# darwin-sonar-sensor.net
KiCad netlist of a schematic drawn in EAGLE
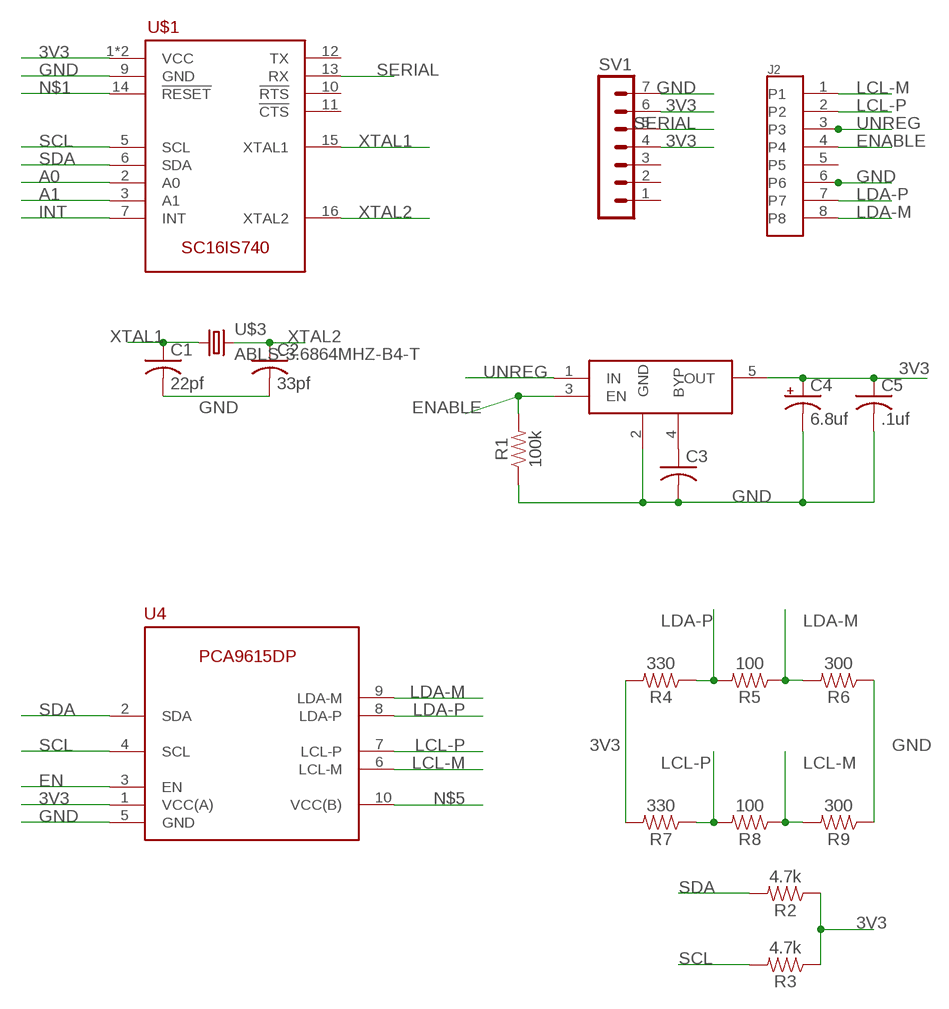
[diagram p0: schematic, sheet 1]

(export (version "E")
  (design (tool "Eeschema 10.0.6"))
  (components
    (comp (ref "C1")
      (value "22pf")
      (footprint "eagle-import:C0603K")
      (libsource (lib "eagle-import") (part "C-USC0603K"))
    )
    (comp (ref "C2")
      (value "33pf")
      (footprint "eagle-import:C0603K")
      (libsource (lib "eagle-import") (part "C-USC0603K"))
    )
    (comp (ref "C3")
      (value "C-USC0603K")
      (footprint "eagle-import:C0603K")
      (libsource (lib "eagle-import") (part "C-USC0603K"))
    )
    (comp (ref "C4")
      (value "6.8uf")
      (footprint "eagle-import:A_3216-18R")
      (libsource (lib "eagle-import") (part "CPOL-USA/3216-18R"))
    )
    (comp (ref "C5")
      (value ".1uf")
      (footprint "eagle-import:C0603K")
      (libsource (lib "eagle-import") (part "C-USC0603K"))
    )
    (comp (ref "J2")
      (value "95501-6889VERT")
      (footprint "eagle-import:85513-5009")
      (libsource (lib "eagle-import") (part "95501-6889VERT"))
    )
    (comp (ref "R1")
      (value "100k")
      (footprint "eagle-import:0603")
      (libsource (lib "eagle-import") (part "100KOHM-0603-1/10W-1%"))
    )
    (comp (ref "R2")
      (value "4.7k")
      (footprint "eagle-import:0603")
      (libsource (lib "eagle-import") (part "100KOHM-0603-1/10W-1%"))
    )
    (comp (ref "R3")
      (value "4.7k")
      (footprint "eagle-import:0603")
      (libsource (lib "eagle-import") (part "100KOHM-0603-1/10W-1%"))
    )
    (comp (ref "R4")
      (value "330")
      (footprint "eagle-import:0603")
      (libsource (lib "eagle-import") (part "100KOHM-0603-1/10W-1%"))
    )
    (comp (ref "R5")
      (value "100")
      (footprint "eagle-import:0603")
      (libsource (lib "eagle-import") (part "100KOHM-0603-1/10W-1%"))
    )
    (comp (ref "R6")
      (value "300")
      (footprint "eagle-import:0603")
      (libsource (lib "eagle-import") (part "100KOHM-0603-1/10W-1%"))
    )
    (comp (ref "R7")
      (value "330")
      (footprint "eagle-import:0603")
      (libsource (lib "eagle-import") (part "100KOHM-0603-1/10W-1%"))
    )
    (comp (ref "R8")
      (value "100")
      (footprint "eagle-import:0603")
      (libsource (lib "eagle-import") (part "100KOHM-0603-1/10W-1%"))
    )
    (comp (ref "R9")
      (value "300")
      (footprint "eagle-import:0603")
      (libsource (lib "eagle-import") (part "100KOHM-0603-1/10W-1%"))
    )
    (comp (ref "SV1")
      (value "MA07-1")
      (footprint "eagle-import:MA07-1")
      (libsource (lib "eagle-import") (part "MA07-1"))
    )
    (comp (ref "U$1")
      (value "SC16IS740")
      (footprint "eagle-import:SOP65P640X110-16")
      (libsource (lib "eagle-import") (part "SC16IS740"))
    )
    (comp (ref "U$3")
      (value "ABLS-3.6864MHZ-B4-T")
      (footprint "eagle-import:ABLS")
      (libsource (lib "eagle-import") (part "ABLS-3.6864MHZ-B4-T"))
    )
    (comp (ref "U$4")
      (value "MIC5219-3.3YM5-TR")
      (footprint "eagle-import:SOT95P280X145-5")
      (libsource (lib "eagle-import") (part "MIC5219-3.3YM5-TR"))
    )
    (comp (ref "U4")
      (value "PCA9615")
      (footprint "eagle-import:SOP50P490X110-10")
      (libsource (lib "eagle-import") (part "PCA9615"))
    )
  )
  (nets
    (net (code "1") (name "/3V3") (class "Default")
      (node (ref "C4") (pin "+") (pinfunction "+_+") (pintype "passive"))
      (node (ref "C5") (pin "1") (pinfunction "1_1") (pintype "passive"))
      (node (ref "R2") (pin "1") (pinfunction "1_1") (pintype "passive"))
      (node (ref "R3") (pin "1") (pinfunction "1_1") (pintype "passive"))
      (node (ref "R4") (pin "2") (pinfunction "2_2") (pintype "passive"))
      (node (ref "R7") (pin "2") (pinfunction "2_2") (pintype "passive"))
      (node (ref "SV1") (pin "4") (pinfunction "4_4") (pintype "passive"))
      (node (ref "SV1") (pin "6") (pinfunction "6_6") (pintype "passive"))
      (node (ref "U$1") (pin "1") (pinfunction "VCC_1") (pintype "bidirectional"))
      (node (ref "U$1") (pin "8") (pinfunction "VCC_8") (pintype "bidirectional"))
      (node (ref "U$4") (pin "5") (pinfunction "OUT_5") (pintype "bidirectional"))
      (node (ref "U4") (pin "1") (pinfunction "VCC(A)_1") (pintype "bidirectional"))
    )
    (net (code "2") (name "/A0") (class "Default")
      (node (ref "U$1") (pin "2") (pinfunction "A0_2") (pintype "bidirectional"))
    )
    (net (code "3") (name "/A1") (class "Default")
      (node (ref "U$1") (pin "3") (pinfunction "A1_3") (pintype "bidirectional"))
    )
    (net (code "4") (name "/EN") (class "Default")
      (node (ref "U4") (pin "3") (pinfunction "EN_3") (pintype "bidirectional"))
    )
    (net (code "5") (name "/ENABLE") (class "Default")
      (node (ref "J2") (pin "4") (pinfunction "P4_4") (pintype "bidirectional"))
      (node (ref "R1") (pin "2") (pinfunction "2_2") (pintype "passive"))
      (node (ref "U$4") (pin "3") (pinfunction "EN_3") (pintype "bidirectional"))
    )
    (net (code "6") (name "/GND") (class "Default")
      (node (ref "C1") (pin "2") (pinfunction "2_2") (pintype "passive"))
      (node (ref "C2") (pin "2") (pinfunction "2_2") (pintype "passive"))
      (node (ref "C3") (pin "2") (pinfunction "2_2") (pintype "passive"))
      (node (ref "C4") (pin "-") (pinfunction "-_-") (pintype "passive"))
      (node (ref "C5") (pin "2") (pinfunction "2_2") (pintype "passive"))
      (node (ref "J2") (pin "6") (pinfunction "P6_6") (pintype "bidirectional"))
      (node (ref "R1") (pin "1") (pinfunction "1_1") (pintype "passive"))
      (node (ref "R6") (pin "1") (pinfunction "1_1") (pintype "passive"))
      (node (ref "R9") (pin "1") (pinfunction "1_1") (pintype "passive"))
      (node (ref "SV1") (pin "7") (pinfunction "7_7") (pintype "passive"))
      (node (ref "U$1") (pin "9") (pinfunction "GND_9") (pintype "bidirectional"))
      (node (ref "U$4") (pin "2") (pinfunction "GND_2") (pintype "bidirectional"))
      (node (ref "U4") (pin "5") (pinfunction "GND_5") (pintype "bidirectional"))
    )
    (net (code "7") (name "/INT") (class "Default")
      (node (ref "U$1") (pin "7") (pinfunction "INT_7") (pintype "bidirectional"))
    )
    (net (code "8") (name "/LCL-M") (class "Default")
      (node (ref "J2") (pin "1") (pinfunction "P1_1") (pintype "bidirectional"))
      (node (ref "R8") (pin "1") (pinfunction "1_1") (pintype "passive"))
      (node (ref "R9") (pin "2") (pinfunction "2_2") (pintype "passive"))
      (node (ref "U4") (pin "6") (pinfunction "LCL-M_6") (pintype "bidirectional"))
    )
    (net (code "9") (name "/LCL-P") (class "Default")
      (node (ref "J2") (pin "2") (pinfunction "P2_2") (pintype "bidirectional"))
      (node (ref "R7") (pin "1") (pinfunction "1_1") (pintype "passive"))
      (node (ref "R8") (pin "2") (pinfunction "2_2") (pintype "passive"))
      (node (ref "U4") (pin "7") (pinfunction "LCL-P_7") (pintype "bidirectional"))
    )
    (net (code "10") (name "/LDA-M") (class "Default")
      (node (ref "J2") (pin "8") (pinfunction "P8_8") (pintype "bidirectional"))
      (node (ref "R5") (pin "1") (pinfunction "1_1") (pintype "passive"))
      (node (ref "R6") (pin "2") (pinfunction "2_2") (pintype "passive"))
      (node (ref "U4") (pin "9") (pinfunction "LDA-M_9") (pintype "bidirectional"))
    )
    (net (code "11") (name "/LDA-P") (class "Default")
      (node (ref "J2") (pin "7") (pinfunction "P7_7") (pintype "bidirectional"))
      (node (ref "R4") (pin "1") (pinfunction "1_1") (pintype "passive"))
      (node (ref "R5") (pin "2") (pinfunction "2_2") (pintype "passive"))
      (node (ref "U4") (pin "8") (pinfunction "LDA-P_8") (pintype "bidirectional"))
    )
    (net (code "12") (name "/N$1") (class "Default")
      (node (ref "U$1") (pin "14") (pinfunction "~{RESET}_14") (pintype "bidirectional"))
    )
    (net (code "13") (name "/N$5") (class "Default")
      (node (ref "U4") (pin "10") (pinfunction "VCC(B)_10") (pintype "bidirectional"))
    )
    (net (code "14") (name "/SCL") (class "Default")
      (node (ref "R3") (pin "2") (pinfunction "2_2") (pintype "passive"))
      (node (ref "U$1") (pin "5") (pinfunction "SCL_5") (pintype "bidirectional"))
      (node (ref "U4") (pin "4") (pinfunction "SCL_4") (pintype "bidirectional"))
    )
    (net (code "15") (name "/SDA") (class "Default")
      (node (ref "R2") (pin "2") (pinfunction "2_2") (pintype "passive"))
      (node (ref "U$1") (pin "6") (pinfunction "SDA_6") (pintype "bidirectional"))
      (node (ref "U4") (pin "2") (pinfunction "SDA_2") (pintype "bidirectional"))
    )
    (net (code "16") (name "/SERIAL") (class "Default")
      (node (ref "SV1") (pin "5") (pinfunction "5_5") (pintype "passive"))
      (node (ref "U$1") (pin "13") (pinfunction "RX_13") (pintype "bidirectional"))
    )
    (net (code "17") (name "/UNREG") (class "Default")
      (node (ref "J2") (pin "3") (pinfunction "P3_3") (pintype "bidirectional"))
      (node (ref "U$4") (pin "1") (pinfunction "IN_1") (pintype "bidirectional"))
    )
    (net (code "18") (name "/XTAL1") (class "Default")
      (node (ref "C1") (pin "1") (pinfunction "1_1") (pintype "passive"))
      (node (ref "U$1") (pin "15") (pinfunction "XTAL1_15") (pintype "bidirectional"))
      (node (ref "U$3") (pin "P$1") (pinfunction "1_P$1") (pintype "passive"))
    )
    (net (code "19") (name "/XTAL2") (class "Default")
      (node (ref "C2") (pin "1") (pinfunction "1_1") (pintype "passive"))
      (node (ref "U$1") (pin "16") (pinfunction "XTAL2_16") (pintype "bidirectional"))
      (node (ref "U$3") (pin "P$2") (pinfunction "2_P$2") (pintype "passive"))
    )
    (net (code "20") (name "Net-(U$4-BYP)") (class "Default")
      (node (ref "C3") (pin "1") (pinfunction "1_1") (pintype "passive"))
      (node (ref "U$4") (pin "4") (pinfunction "BYP_4") (pintype "bidirectional"))
    )
    (net (code "21") (name "unconnected-(J2-P5-Pad5)") (class "Default")
      (node (ref "J2") (pin "5") (pinfunction "P5_5") (pintype "bidirectional"))
    )
    (net (code "22") (name "unconnected-(SV1-Pad1)") (class "Default")
      (node (ref "SV1") (pin "1") (pinfunction "1_1") (pintype "passive"))
    )
    (net (code "23") (name "unconnected-(SV1-Pad2)") (class "Default")
      (node (ref "SV1") (pin "2") (pinfunction "2_2") (pintype "passive"))
    )
    (net (code "24") (name "unconnected-(SV1-Pad3)") (class "Default")
      (node (ref "SV1") (pin "3") (pinfunction "3_3") (pintype "passive"))
    )
    (net (code "25") (name "unconnected-(U$1-TX-Pad12)") (class "Default")
      (node (ref "U$1") (pin "12") (pinfunction "TX_12") (pintype "bidirectional"))
    )
    (net (code "26") (name "unconnected-(U$1-~{CTS}-Pad11)") (class "Default")
      (node (ref "U$1") (pin "11") (pinfunction "~{CTS}_11") (pintype "bidirectional"))
    )
    (net (code "27") (name "unconnected-(U$1-~{RTS}-Pad10)") (class "Default")
      (node (ref "U$1") (pin "10") (pinfunction "~{RTS}_10") (pintype "bidirectional"))
    )
  )
)
